# Barun_Gas_Control.net
KiCad netlist of a schematic drawn in Altium Designer
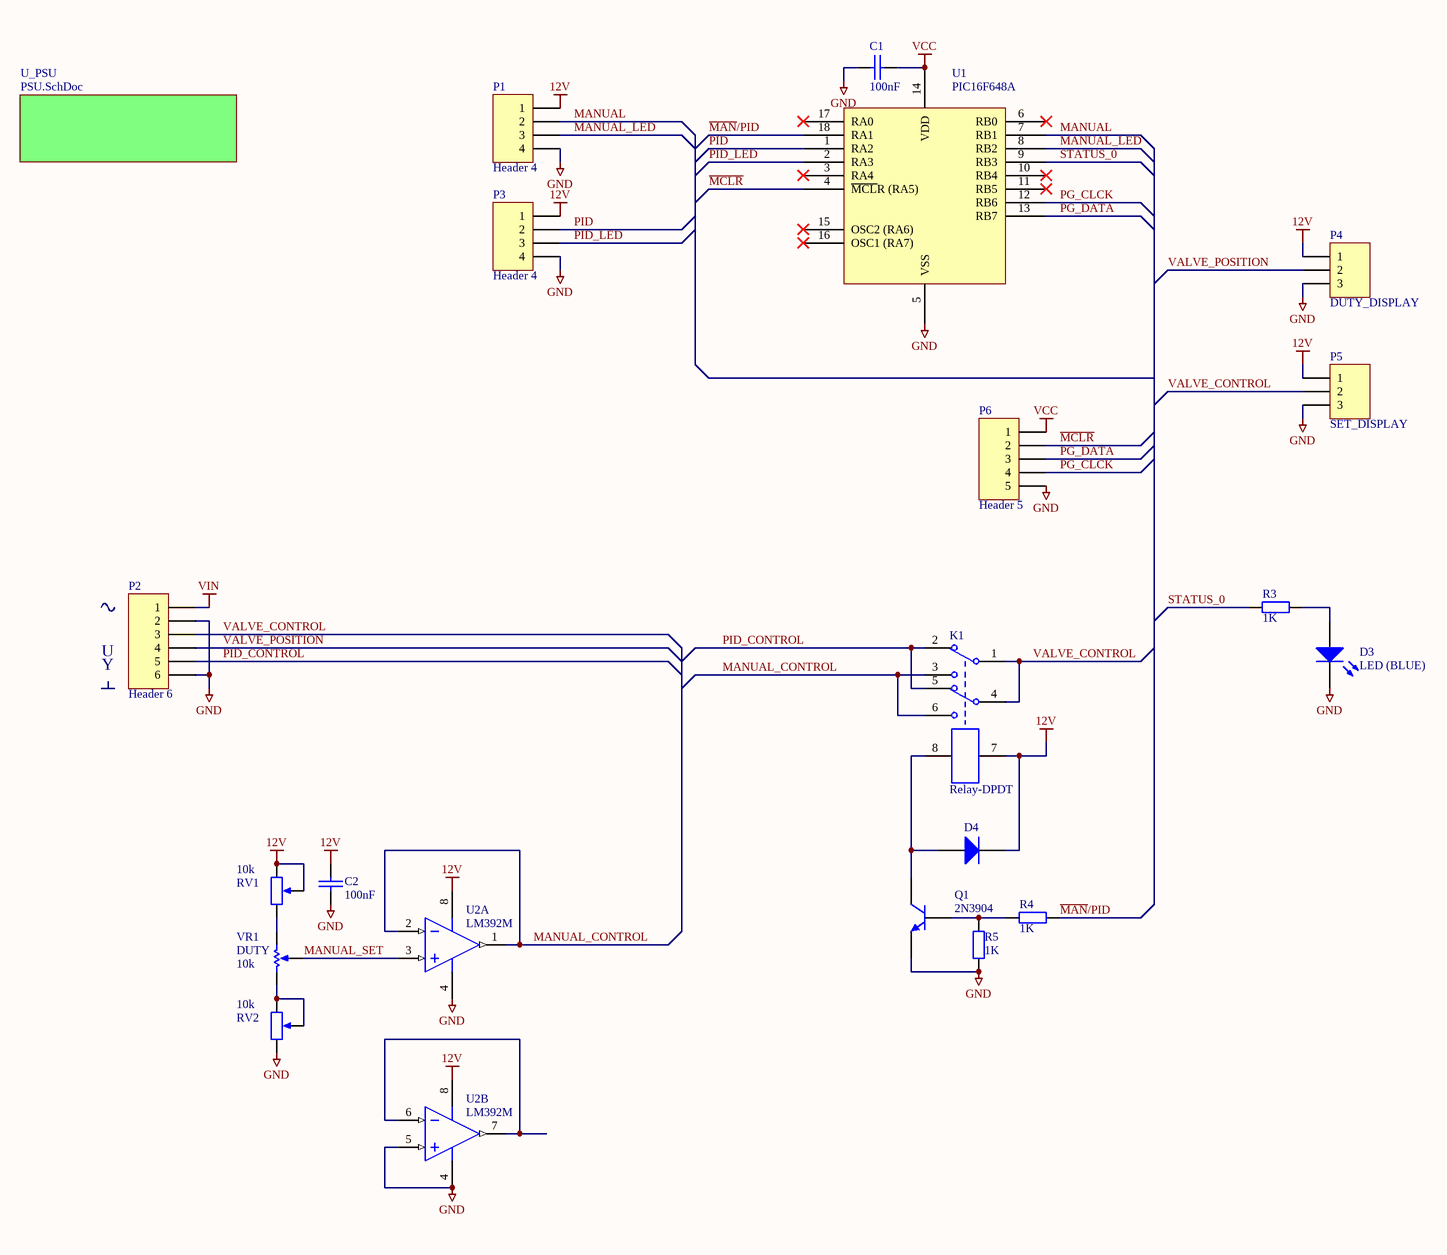
[diagram p0: Barun Gas Control.SchDoc]

(export (version "E")
  (design (tool "Eeschema 10.0.6"))
  (components
    (comp (ref "C1")
      (value "100nF")
      (footprint "CAP RADIAL 0.200")
      (description "CAPACITOR SMD 0402")
      (libsource (lib "401 CCPA") (part "CAP"))
    )
    (comp (ref "C2")
      (value "100nF")
      (footprint "CAP RADIAL 0.200")
      (description "CAPACITOR SMD 0402")
      (libsource (lib "401 CCPA") (part "CAP"))
    )
    (comp (ref "D3")
      (value "LED (BLUE)")
      (footprint "LED(3D) 5MM VERTICAL (GREEN)")
      (description "3mm RED LED")
      (fields (field (name "MOUSER PART NO.") "604-WP132XIT") (field (name "FARNELL PART NO.") "1003393"))
      (libsource (lib "NASCO") (part "LED 3mm RED"))
    )
    (comp (ref "D4")
      (value "Diode 1N4148")
      (footprint "DO-35")
      (description "High Conductance Fast Diode")
      (fields (field (name "PUBLISHER") "Altium Limited"))
      (libsource (lib "Miscellaneous Devices") (part "Diode 1N4148"))
    )
    (comp (ref "K1")
      (value "Relay-DPDT")
      (footprint "RELAY DPDT")
      (description "DS2Y-S-DC12V")
      (fields (field (name "MANUFACTURER") "Generic Components"))
      (libsource (lib "401 CCPA") (part "Relay-DPDT"))
    )
    (comp (ref "P1")
      (value "Header 4")
      (footprint "HDR1X4")
      (description "Header, 4-Pin")
      (fields (field (name "PUBLISHER") "Altium Limited"))
      (libsource (lib "Miscellaneous Connectors") (part "Header 4"))
    )
    (comp (ref "P2")
      (value "Header 6")
      (footprint "6 x 5.08mm")
      (description "Header, 6-Pin")
      (fields (field (name "PUBLISHER") "Altium Limited"))
      (libsource (lib "Miscellaneous Connectors") (part "Header 6"))
    )
    (comp (ref "P3")
      (value "Header 4")
      (footprint "HDR1X4")
      (description "Header, 4-Pin")
      (fields (field (name "PUBLISHER") "Altium Limited"))
      (libsource (lib "Miscellaneous Connectors") (part "Header 4"))
    )
    (comp (ref "P4")
      (value "DUTY_DISPLAY")
      (footprint "HDR1X3")
      (description "Header, 3-Pin")
      (fields (field (name "PUBLISHER") "Altium Limited"))
      (libsource (lib "Miscellaneous Connectors") (part "Header 3"))
    )
    (comp (ref "P5")
      (value "SET_DISPLAY")
      (footprint "HDR1X3")
      (description "Header, 3-Pin")
      (fields (field (name "PUBLISHER") "Altium Limited"))
      (libsource (lib "Miscellaneous Connectors") (part "Header 3"))
    )
    (comp (ref "P6")
      (value "Header 5")
      (footprint "HDR1X5")
      (description "Header, 5-Pin")
      (fields (field (name "PUBLISHER") "Altium Limited"))
      (libsource (lib "Miscellaneous Connectors") (part "Header 5"))
    )
    (comp (ref "Q1")
      (value "2N3904")
      (footprint "TO-92A")
      (description "NPN General Purpose Amplifier")
      (fields (field (name "PUBLISHER") "Altium Limited"))
      (libsource (lib "Miscellaneous Devices") (part "2N3904"))
    )
    (comp (ref "R3")
      (value "1K")
      (footprint "AXIAL-0.4")
      (description "Resistor")
      (fields (field (name "Comment") "Res2") (field (name "PUBLISHER") "Altium Limited"))
      (libsource (lib "Miscellaneous Devices") (part "Res2"))
    )
    (comp (ref "R4")
      (value "1K")
      (footprint "AXIAL-0.4")
      (description "Resistor")
      (fields (field (name "Comment") "Res2") (field (name "PUBLISHER") "Altium Limited"))
      (libsource (lib "Miscellaneous Devices") (part "Res2"))
    )
    (comp (ref "R5")
      (value "1K")
      (footprint "AXIAL-0.4")
      (description "Resistor")
      (fields (field (name "Comment") "Res2") (field (name "PUBLISHER") "Altium Limited"))
      (libsource (lib "") (part "Res2_1"))
    )
    (comp (ref "RV1")
      (value "10k")
      (footprint "TRIMMER")
      (description "Variable Resistor")
      (libsource (lib "NASCO") (part "VAR (POT) SMD"))
    )
    (comp (ref "RV2")
      (value "10k")
      (footprint "TRIMMER")
      (description "Variable Resistor")
      (libsource (lib "NASCO") (part "VAR (POT) SMD"))
    )
    (comp (ref "U1")
      (value "PIC16F648A")
      (footprint "DIP-18")
      (description "PIC16F88")
      (fields
        (field (name "MOUSER PART NO.") "579-PIC16F88-E/SS")
        (field (name "FARNELL PART NO.") "9761519")
      )
      (libsource (lib "NASCO") (part "PIC16F87/88"))
    )
    (comp (ref "U2")
      (value "LM392M")
      (footprint "DIP_8")
      (description "Low Power Operational Amplifier/Voltage Comparator, 8-pin Narrow SOIC")
      (fields
        (field (name "MANUFACTURER") "National Semiconductor")
        (field (name "PUBLISHER") "Altium Limited")
      )
      (libsource (lib "NSC Amplifier") (part "LM392M"))
    )
    (comp (ref "VR1")
      (value "DUTY")
      (footprint "HDR1X3")
      (description "Potentiometer")
      (fields (field (name "ALTIUM_VALUE") "10k") (field (name "PUBLISHER") "Altium Limited"))
      (libsource (lib "Miscellaneous Devices") (part "RPot"))
    )
  )
  (nets
    (net (code "1") (name "/MANUAL") (class "Default")
      (node (ref "P1") (pin "2") (pinfunction "2_2") (pintype "passive"))
      (node (ref "U1") (pin "7") (pinfunction "RB1_7") (pintype "passive"))
    )
    (net (code "2") (name "/MANUAL_CONTROL") (class "Default")
      (node (ref "K1") (pin "3") (pinfunction "3_3") (pintype "passive"))
      (node (ref "K1") (pin "6") (pinfunction "6_6") (pintype "passive"))
      (node (ref "U2") (pin "1") (pinfunction "OUTA_1") (pintype "output"))
      (node (ref "U2") (pin "2") (pinfunction "INA-_2") (pintype "input"))
    )
    (net (code "3") (name "/MANUAL_LED") (class "Default")
      (node (ref "P1") (pin "3") (pinfunction "3_3") (pintype "passive"))
      (node (ref "U1") (pin "8") (pinfunction "RB2_8") (pintype "passive"))
    )
    (net (code "4") (name "/MANUAL_SET") (class "Default")
      (node (ref "U2") (pin "3") (pinfunction "INA+_3") (pintype "input"))
      (node (ref "VR1") (pin "3") (pinfunction "TAP_3") (pintype "passive"))
    )
    (net (code "5") (name "/MCLR") (class "Default")
      (node (ref "P6") (pin "2") (pinfunction "2_2") (pintype "passive"))
      (node (ref "U1") (pin "4") (pinfunction "~{MCL}R_(RA5)_4") (pintype "passive"))
    )
    (net (code "6") (name "/PG_CLCK") (class "Default")
      (node (ref "P6") (pin "4") (pinfunction "4_4") (pintype "passive"))
      (node (ref "U1") (pin "12") (pinfunction "RB6_12") (pintype "passive"))
    )
    (net (code "7") (name "/PG_DATA") (class "Default")
      (node (ref "P6") (pin "3") (pinfunction "3_3") (pintype "passive"))
      (node (ref "U1") (pin "13") (pinfunction "RB7_13") (pintype "passive"))
    )
    (net (code "8") (name "/PID") (class "Default")
      (node (ref "P3") (pin "2") (pinfunction "2_2") (pintype "passive"))
      (node (ref "U1") (pin "1") (pinfunction "RA2_1") (pintype "passive"))
    )
    (net (code "9") (name "/PID_CONTROL") (class "Default")
      (node (ref "K1") (pin "2") (pinfunction "2_2") (pintype "passive"))
      (node (ref "K1") (pin "5") (pinfunction "5_5") (pintype "passive"))
      (node (ref "P2") (pin "5") (pinfunction "5_5") (pintype "passive"))
    )
    (net (code "10") (name "/PID_LED") (class "Default")
      (node (ref "P3") (pin "3") (pinfunction "3_3") (pintype "passive"))
      (node (ref "U1") (pin "2") (pinfunction "RA3_2") (pintype "passive"))
    )
    (net (code "11") (name "/STATUS_0") (class "Default")
      (node (ref "R3") (pin "2") (pinfunction "2_2") (pintype "passive"))
      (node (ref "U1") (pin "9") (pinfunction "RB3_9") (pintype "passive"))
    )
    (net (code "12") (name "/VALVE_CONTROL") (class "Default")
      (node (ref "K1") (pin "1") (pinfunction "1_1") (pintype "passive"))
      (node (ref "K1") (pin "4") (pinfunction "4_4") (pintype "passive"))
      (node (ref "P2") (pin "3") (pinfunction "3_3") (pintype "passive"))
      (node (ref "P5") (pin "2") (pinfunction "2_2") (pintype "passive"))
    )
    (net (code "13") (name "/VALVE_POSITION") (class "Default")
      (node (ref "P2") (pin "4") (pinfunction "4_4") (pintype "passive"))
      (node (ref "P4") (pin "2") (pinfunction "2_2") (pintype "passive"))
    )
    (net (code "14") (name "/~{MAN}{slash}PID") (class "Default")
      (node (ref "R4") (pin "1") (pinfunction "1_1") (pintype "passive"))
      (node (ref "U1") (pin "18") (pinfunction "RA1_18") (pintype "passive"))
    )
    (net (code "15") (name "12V") (class "Default")
      (node (ref "C2") (pin "2") (pinfunction "2_2") (pintype "passive"))
      (node (ref "D4") (pin "2") (pinfunction "K_2") (pintype "passive"))
      (node (ref "K1") (pin "7") (pinfunction "7_7") (pintype "passive"))
      (node (ref "P1") (pin "1") (pinfunction "1_1") (pintype "passive"))
      (node (ref "P3") (pin "1") (pinfunction "1_1") (pintype "passive"))
      (node (ref "P4") (pin "1") (pinfunction "1_1") (pintype "passive"))
      (node (ref "P5") (pin "1") (pinfunction "1_1") (pintype "passive"))
      (node (ref "RV1") (pin "1") (pinfunction "1_1") (pintype "passive"))
      (node (ref "RV1") (pin "2") (pinfunction "2_2") (pintype "passive"))
      (node (ref "U2") (pin "8") (pinfunction "V+_8") (pintype "power_in"))
    )
    (net (code "16") (name "GND") (class "Default")
      (node (ref "C1") (pin "1") (pinfunction "1_1") (pintype "passive"))
      (node (ref "C2") (pin "1") (pinfunction "1_1") (pintype "passive"))
      (node (ref "D3") (pin "2") (pinfunction "K_2") (pintype "passive"))
      (node (ref "P1") (pin "4") (pinfunction "4_4") (pintype "passive"))
      (node (ref "P2") (pin "2") (pinfunction "2_2") (pintype "passive"))
      (node (ref "P2") (pin "6") (pinfunction "6_6") (pintype "passive"))
      (node (ref "P3") (pin "4") (pinfunction "4_4") (pintype "passive"))
      (node (ref "P4") (pin "3") (pinfunction "3_3") (pintype "passive"))
      (node (ref "P5") (pin "3") (pinfunction "3_3") (pintype "passive"))
      (node (ref "P6") (pin "5") (pinfunction "5_5") (pintype "passive"))
      (node (ref "Q1") (pin "1") (pinfunction "E_1") (pintype "passive"))
      (node (ref "R5") (pin "1") (pinfunction "1_1") (pintype "passive"))
      (node (ref "RV2") (pin "3") (pinfunction "3_3") (pintype "passive"))
      (node (ref "U1") (pin "5") (pinfunction "VSS_5") (pintype "passive"))
      (node (ref "U2") (pin "4") (pinfunction "GND_4") (pintype "power_in"))
      (node (ref "U2") (pin "5") (pinfunction "INB+_5") (pintype "input"))
    )
    (net (code "17") (name "Net-(D3-A)") (class "Default")
      (node (ref "D3") (pin "1") (pinfunction "A_1") (pintype "passive"))
      (node (ref "R3") (pin "1") (pinfunction "1_1") (pintype "passive"))
    )
    (net (code "18") (name "Net-(D4-A)") (class "Default")
      (node (ref "D4") (pin "1") (pinfunction "A_1") (pintype "passive"))
      (node (ref "K1") (pin "8") (pinfunction "8_8") (pintype "passive"))
      (node (ref "Q1") (pin "3") (pinfunction "C_3") (pintype "passive"))
    )
    (net (code "19") (name "Net-(Q1-B)") (class "Default")
      (node (ref "Q1") (pin "2") (pinfunction "B_2") (pintype "passive"))
      (node (ref "R4") (pin "2") (pinfunction "2_2") (pintype "passive"))
      (node (ref "R5") (pin "2") (pinfunction "2_2") (pintype "passive"))
    )
    (net (code "20") (name "Net-(U2B-INB-)") (class "Default")
      (node (ref "U2") (pin "6") (pinfunction "INB-_6") (pintype "input"))
      (node (ref "U2") (pin "7") (pinfunction "OUTB_7") (pintype "output"))
    )
    (net (code "21") (name "Net-(VR1-BOT)") (class "Default")
      (node (ref "RV2") (pin "1") (pinfunction "1_1") (pintype "passive"))
      (node (ref "RV2") (pin "2") (pinfunction "2_2") (pintype "passive"))
      (node (ref "VR1") (pin "2") (pinfunction "BOT_2") (pintype "passive"))
    )
    (net (code "22") (name "Net-(VR1-TOP)") (class "Default")
      (node (ref "RV1") (pin "3") (pinfunction "3_3") (pintype "passive"))
      (node (ref "VR1") (pin "1") (pinfunction "TOP_1") (pintype "passive"))
    )
    (net (code "23") (name "VCC") (class "Default")
      (node (ref "C1") (pin "2") (pinfunction "2_2") (pintype "passive"))
      (node (ref "P6") (pin "1") (pinfunction "1_1") (pintype "passive"))
      (node (ref "U1") (pin "14") (pinfunction "VDD_14") (pintype "passive"))
    )
    (net (code "24") (name "VIN") (class "Default")
      (node (ref "P2") (pin "1") (pinfunction "1_1") (pintype "passive"))
    )
    (net (code "25") (name "unconnected-(U1-OSC1_(RA7)-Pad16)") (class "Default")
      (node (ref "U1") (pin "16") (pinfunction "OSC1_(RA7)_16") (pintype "passive+no_connect"))
    )
    (net (code "26") (name "unconnected-(U1-OSC2_(RA6)-Pad15)") (class "Default")
      (node (ref "U1") (pin "15") (pinfunction "OSC2_(RA6)_15") (pintype "passive+no_connect"))
    )
    (net (code "27") (name "unconnected-(U1-RA0-Pad17)") (class "Default")
      (node (ref "U1") (pin "17") (pinfunction "RA0_17") (pintype "passive+no_connect"))
    )
    (net (code "28") (name "unconnected-(U1-RA4-Pad3)") (class "Default")
      (node (ref "U1") (pin "3") (pinfunction "RA4_3") (pintype "passive+no_connect"))
    )
    (net (code "29") (name "unconnected-(U1-RB0-Pad6)") (class "Default")
      (node (ref "U1") (pin "6") (pinfunction "RB0_6") (pintype "passive+no_connect"))
    )
    (net (code "30") (name "unconnected-(U1-RB4-Pad10)") (class "Default")
      (node (ref "U1") (pin "10") (pinfunction "RB4_10") (pintype "passive+no_connect"))
    )
    (net (code "31") (name "unconnected-(U1-RB5-Pad11)") (class "Default")
      (node (ref "U1") (pin "11") (pinfunction "RB5_11") (pintype "passive+no_connect"))
    )
  )
)
